# MCU.net
KiCad netlist of a schematic drawn in Altium Designer
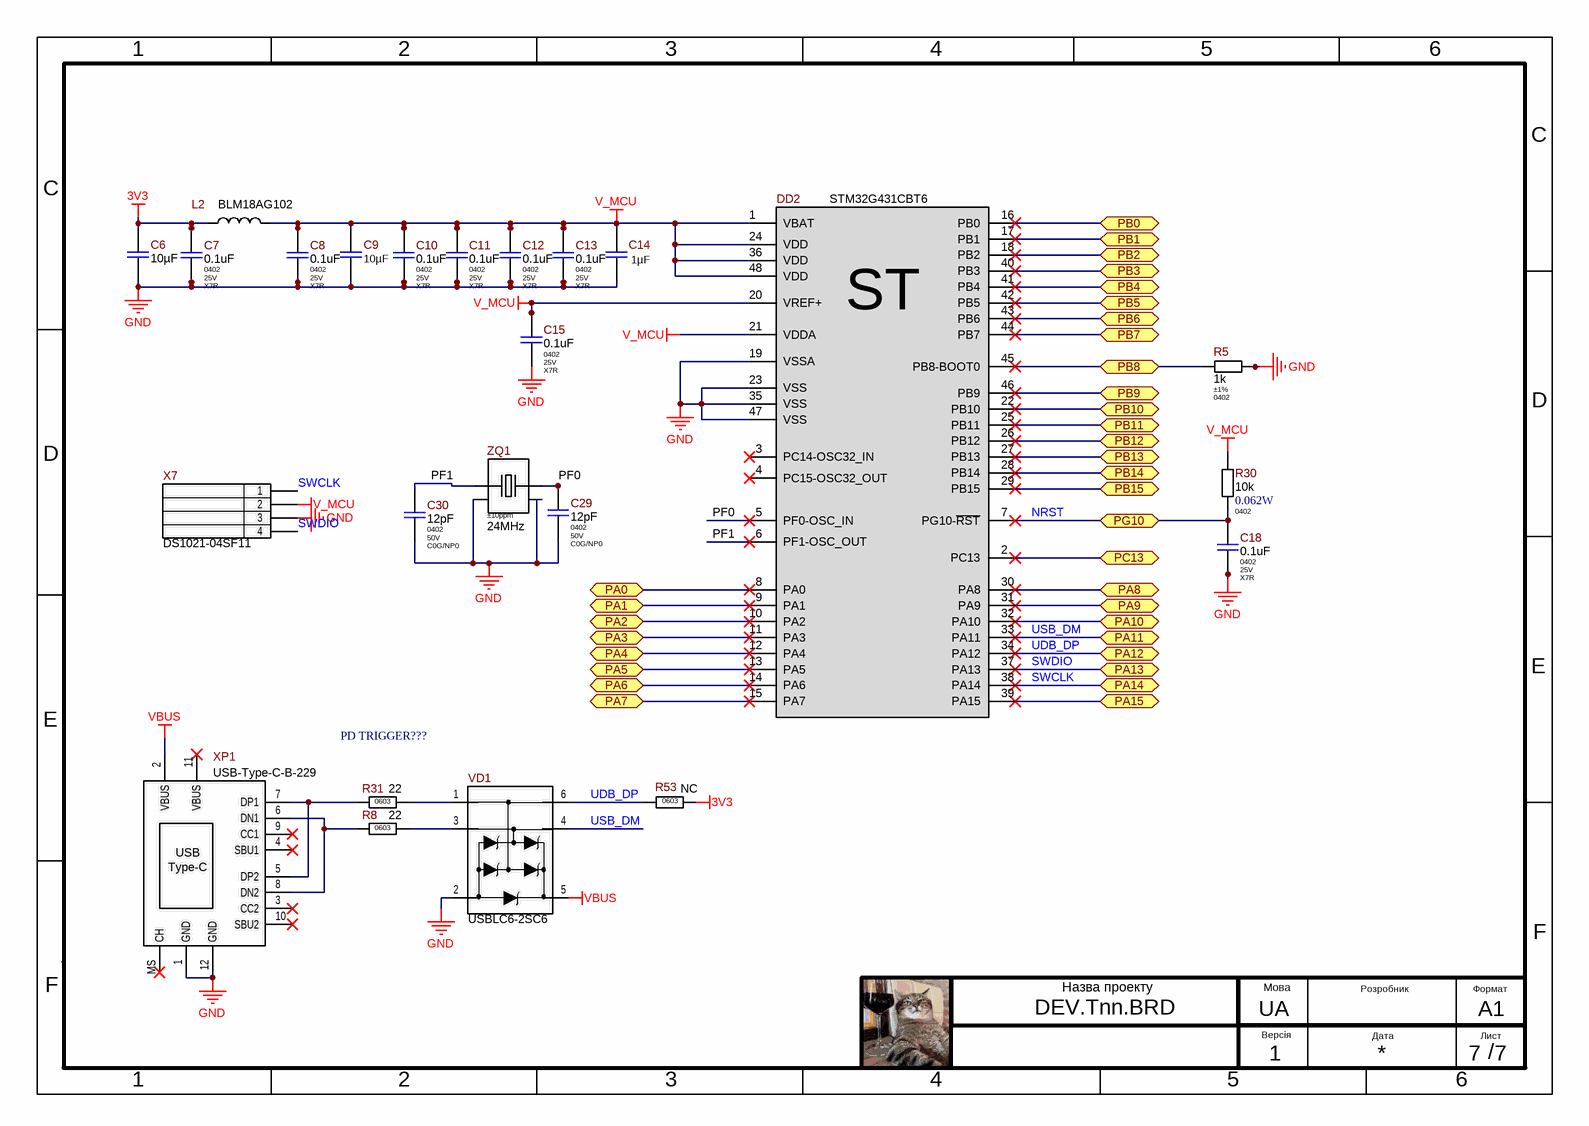
[diagram p0: MCU.SchDoc]

(export (version "E")
  (design (tool "Eeschema 10.0.6"))
  (components
    (comp (ref "C6")
      (value "10µF")
      (footprint "C0603(1608)")
      (description "CAP CER 10UF 6.3V X5R 0603")
      (fields (field (name "PART NUMBER") "10µF  6.3V C0603") (field (name "TOLERANCE") "±20%"))
      (libsource (lib "Database") (part "Capacitor_Ceramic"))
    )
    (comp (ref "C7")
      (value "0.1uF")
      (footprint "C_CERAMIC_0402_MED")
      (description "100nF 25V X7R ±10% 0402 Ceramic Capacitor RoHS")
      (fields
        (field (name "PART NUMBER") "GRM155R71E104KE14J")
        (field (name "TOLERANCE") "±10%")
        (field (name "PACKAGE") "0402")
        (field (name "VOLTAGE") "25V")
        (field (name "DIELECTRIC TYPE") "X7R")
      )
      (libsource (lib "AjaxLibrary") (part "Capacitor-NonPolar"))
    )
    (comp (ref "C8")
      (value "0.1uF")
      (footprint "C_CERAMIC_0402_MED")
      (description "100nF 25V X7R ±10% 0402 Ceramic Capacitor RoHS")
      (fields
        (field (name "PART NUMBER") "GRM155R71E104KE14J")
        (field (name "TOLERANCE") "±10%")
        (field (name "PACKAGE") "0402")
        (field (name "VOLTAGE") "25V")
        (field (name "DIELECTRIC TYPE") "X7R")
      )
      (libsource (lib "AjaxLibrary") (part "Capacitor-NonPolar"))
    )
    (comp (ref "C9")
      (value "10µF")
      (footprint "C0603(1608)")
      (description "CAP CER 10UF 6.3V X5R 0603")
      (fields (field (name "PART NUMBER") "10µF  6.3V C0603") (field (name "TOLERANCE") "±20%"))
      (libsource (lib "Database") (part "Capacitor_Ceramic"))
    )
    (comp (ref "C10")
      (value "0.1uF")
      (footprint "C_CERAMIC_0402_MED")
      (description "100nF 25V X7R ±10% 0402 Ceramic Capacitor RoHS")
      (fields
        (field (name "PART NUMBER") "GRM155R71E104KE14J")
        (field (name "TOLERANCE") "±10%")
        (field (name "PACKAGE") "0402")
        (field (name "VOLTAGE") "25V")
        (field (name "DIELECTRIC TYPE") "X7R")
      )
      (libsource (lib "AjaxLibrary") (part "Capacitor-NonPolar"))
    )
    (comp (ref "C11")
      (value "0.1uF")
      (footprint "C_CERAMIC_0402_MED")
      (description "100nF 25V X7R ±10% 0402 Ceramic Capacitor RoHS")
      (fields
        (field (name "PART NUMBER") "GRM155R71E104KE14J")
        (field (name "TOLERANCE") "±10%")
        (field (name "PACKAGE") "0402")
        (field (name "VOLTAGE") "25V")
        (field (name "DIELECTRIC TYPE") "X7R")
      )
      (libsource (lib "AjaxLibrary") (part "Capacitor-NonPolar"))
    )
    (comp (ref "C12")
      (value "0.1uF")
      (footprint "C_CERAMIC_0402_MED")
      (description "100nF 25V X7R ±10% 0402 Ceramic Capacitor RoHS")
      (fields
        (field (name "PART NUMBER") "GRM155R71E104KE14J")
        (field (name "TOLERANCE") "±10%")
        (field (name "PACKAGE") "0402")
        (field (name "VOLTAGE") "25V")
        (field (name "DIELECTRIC TYPE") "X7R")
      )
      (libsource (lib "AjaxLibrary") (part "Capacitor-NonPolar"))
    )
    (comp (ref "C13")
      (value "0.1uF")
      (footprint "C_CERAMIC_0402_MED")
      (description "100nF 25V X7R ±10% 0402 Ceramic Capacitor RoHS")
      (fields
        (field (name "PART NUMBER") "GRM155R71E104KE14J")
        (field (name "TOLERANCE") "±10%")
        (field (name "PACKAGE") "0402")
        (field (name "VOLTAGE") "25V")
        (field (name "DIELECTRIC TYPE") "X7R")
      )
      (libsource (lib "AjaxLibrary") (part "Capacitor-NonPolar"))
    )
    (comp (ref "C14")
      (value "1µF")
      (footprint "C0603(1608)")
      (description "CAP CER 1UF 25V X5R 0603")
      (fields (field (name "PART NUMBER") "1µF  25V C0603") (field (name "TOLERANCE") "±10%"))
      (libsource (lib "Database") (part "Capacitor_Ceramic"))
    )
    (comp (ref "C15")
      (value "0.1uF")
      (footprint "C_CERAMIC_0402_MED")
      (description "100nF 25V X7R ±10% 0402 Ceramic Capacitor RoHS")
      (fields
        (field (name "PART NUMBER") "GRM155R71E104KE14J")
        (field (name "TOLERANCE") "±10%")
        (field (name "PACKAGE") "0402")
        (field (name "VOLTAGE") "25V")
        (field (name "DIELECTRIC TYPE") "X7R")
      )
      (libsource (lib "AjaxLibrary") (part "Capacitor-NonPolar"))
    )
    (comp (ref "C18")
      (value "0.1uF")
      (footprint "C_CERAMIC_0402_MED")
      (description "100nF 25V X7R ±10% 0402 Ceramic Capacitor RoHS")
      (fields
        (field (name "PART NUMBER") "GRM155R71E104KE14J")
        (field (name "TOLERANCE") "±10%")
        (field (name "PACKAGE") "0402")
        (field (name "VOLTAGE") "25V")
        (field (name "DIELECTRIC TYPE") "X7R")
      )
      (libsource (lib "AjaxLibrary") (part "Capacitor-NonPolar"))
    )
    (comp (ref "C29")
      (value "12pF")
      (footprint "C_CERAMIC_0402_MED")
      (description "12pF 50V C0G ±5% 0402 Ceramic Capacitor RoHS")
      (fields
        (field (name "PART NUMBER") "CL05C120JB5NNNC")
        (field (name "TOLERANCE") "±5%")
        (field (name "PACKAGE") "0402")
        (field (name "VOLTAGE") "50V")
        (field (name "DIELECTRIC TYPE") "C0G/NP0")
      )
      (libsource (lib "AjaxLibrary") (part "Capacitor-NonPolar"))
    )
    (comp (ref "C30")
      (value "12pF")
      (footprint "C_CERAMIC_0402_MED")
      (description "12pF 50V C0G ±5% 0402 Ceramic Capacitor RoHS")
      (fields
        (field (name "PART NUMBER") "CL05C120JB5NNNC")
        (field (name "TOLERANCE") "±5%")
        (field (name "PACKAGE") "0402")
        (field (name "VOLTAGE") "50V")
        (field (name "DIELECTRIC TYPE") "C0G/NP0")
      )
      (libsource (lib "AjaxLibrary") (part "Capacitor-NonPolar"))
    )
    (comp (ref "DD2")
      (value "STM32G431CBT6")
      (footprint "LQFP48")
      (fields (field (name "MF") "STMicroelectronics") (field (name "MP") "STM32G431CBU6"))
      (libsource (lib "Database") (part "STM32G431CBT6"))
    )
    (comp (ref "L2")
      (value "BLM18AG102")
      (footprint "BLM18(0603)")
      (description "FERRITE BEAD 1 KOHM 0603 1LN")
      (fields
        (field (name "TOLERANCE") "±25%")
        (field (name "MANUFACTURER") "Murata Electronics North America")
      )
      (libsource (lib "Database") (part "INDUCTORS"))
    )
    (comp (ref "R5")
      (value "1k")
      (footprint "R_ANY_CHIP_0402_MED")
      (description "1 kOhms ±1% 1/16W 0402 Thick Film Resistor")
      (fields
        (field (name "TOLERANCE") "±1%")
        (field (name "PART NUMBER") "RC0402FR-071KL")
        (field (name "PACKAGE") "0402")
        (field (name "MANUFACTURER") "Yageo")
      )
      (libsource (lib "AjaxLibrary") (part "Resistor"))
    )
    (comp (ref "R8")
      (value "22")
      (footprint "R0603")
      (description "RES SMD 22 OHM  ±1% 1/10W 0603")
      (fields
        (field (name "PACKAGE/CASE") "0603")
        (field (name "PART NUMBER") "22  R0603")
        (field (name "TOLERANCE") "±1%")
      )
      (libsource (lib "Database") (part "R0603"))
    )
    (comp (ref "R30")
      (value "10k")
      (footprint "R_ANY_CHIP_0402_MED")
      (description "10 kOhms ±5% 1/16W 0402 Thick Film Resistor")
      (fields
        (field (name "PART NUMBER") "RC0402JR-0710KL")
        (field (name "TOLERANCE") "±5%")
        (field (name "POWER RATING") "0.062W")
        (field (name "PACKAGE") "0402")
      )
      (libsource (lib "AjaxLibrary") (part "Resistor"))
    )
    (comp (ref "R31")
      (value "22")
      (footprint "R0603")
      (description "RES SMD 22 OHM  ±1% 1/10W 0603")
      (fields
        (field (name "PACKAGE/CASE") "0603")
        (field (name "PART NUMBER") "22  R0603")
        (field (name "TOLERANCE") "±1%")
      )
      (libsource (lib "Database") (part "R0603"))
    )
    (comp (ref "R53")
      (value "NC")
      (footprint "R0603")
      (description "RES SMD 1.5 k OHM  ±1% 1/10W 0603")
      (fields (field (name "PART NUMBER") "1.5 k  R0603") (field (name "PACKAGE/CASE") "0603"))
      (libsource (lib "Database") (part "R0603"))
    )
    (comp (ref "VD1")
      (value "USBLC6-2SC6")
      (footprint "SOT-23-6")
      (description "TVS DIODE 5.25V 17V SOT23-6")
      (fields (field (name "MANUFACTURER") "STMicroelectronics"))
      (libsource (lib "Database") (part "USBLC6-2"))
    )
    (comp (ref "X7")
      (value "PLS-4 (Part of PLS-40)")
      (footprint "DS1021-04S")
      (description "4 Pin 2.54mm Male Header, Vertical, 3mm and 6.1mm, PLS-4")
      (fields (field (name "PART NUMBER") "DS1021-04SF11") (field (name "MANUFACTURER") "Connfly"))
      (libsource (lib "AjaxLibrary") (part "General-4-Pin"))
    )
    (comp (ref "XP1")
      (value "USB-Type-C-B-229")
      (footprint "USB-Type-C-B-229")
      (fields (field (name "MANUFACTURER") "KLS ELECTRONIC CO., LTD."))
      (libsource (lib "Database") (part "USB-Type-C-B-229"))
    )
    (comp (ref "ZQ1")
      (value "C3E-24.000-18-1010-R")
      (footprint "CXA-321_REC")
      (description "24MHz, 18pF, ±10ppm, 100Ohm ESR, 100uW DL Crystal Quartz")
      (fields
        (field (name "FREQUENCY TOLERANCE") "±10ppm")
        (field (name "FREQUENCY") "24MHz")
        (field (name "MANUFACTURER") "Aker")
      )
      (libsource (lib "AjaxLibrary") (part "Crystal-Quartz-4-Pin-01"))
    )
  )
  (nets
    (net (code "1") (name "/NRST") (class "Default")
      (node (ref "C18") (pin "2") (pinfunction "2_2") (pintype "passive"))
      (node (ref "DD2") (pin "7") (pinfunction "PG10-~{RST}_7") (pintype "passive"))
      (node (ref "R30") (pin "2") (pintype "passive"))
    )
    (net (code "2") (name "/PA0") (class "Default")
      (node (ref "DD2") (pin "8") (pinfunction "PA0_8") (pintype "passive+no_connect"))
    )
    (net (code "3") (name "/PA1") (class "Default")
      (node (ref "DD2") (pin "9") (pinfunction "PA1_9") (pintype "passive+no_connect"))
    )
    (net (code "4") (name "/PA2") (class "Default")
      (node (ref "DD2") (pin "10") (pinfunction "PA2_10") (pintype "passive+no_connect"))
    )
    (net (code "5") (name "/PA3") (class "Default")
      (node (ref "DD2") (pin "11") (pinfunction "PA3_11") (pintype "passive+no_connect"))
    )
    (net (code "6") (name "/PA4") (class "Default")
      (node (ref "DD2") (pin "12") (pinfunction "PA4_12") (pintype "passive+no_connect"))
    )
    (net (code "7") (name "/PA5") (class "Default")
      (node (ref "DD2") (pin "13") (pinfunction "PA5_13") (pintype "passive+no_connect"))
    )
    (net (code "8") (name "/PA6") (class "Default")
      (node (ref "DD2") (pin "14") (pinfunction "PA6_14") (pintype "passive+no_connect"))
    )
    (net (code "9") (name "/PA7") (class "Default")
      (node (ref "DD2") (pin "15") (pinfunction "PA7_15") (pintype "passive+no_connect"))
    )
    (net (code "10") (name "/PA8") (class "Default")
      (node (ref "DD2") (pin "30") (pinfunction "PA8_30") (pintype "passive+no_connect"))
    )
    (net (code "11") (name "/PA9") (class "Default")
      (node (ref "DD2") (pin "31") (pinfunction "PA9_31") (pintype "passive+no_connect"))
    )
    (net (code "12") (name "/PA10") (class "Default")
      (node (ref "DD2") (pin "32") (pinfunction "PA10_32") (pintype "passive+no_connect"))
    )
    (net (code "13") (name "/PA15") (class "Default")
      (node (ref "DD2") (pin "39") (pinfunction "PA15_39") (pintype "passive+no_connect"))
    )
    (net (code "14") (name "/PB0") (class "Default")
      (node (ref "DD2") (pin "16") (pinfunction "PB0_16") (pintype "passive+no_connect"))
    )
    (net (code "15") (name "/PB1") (class "Default")
      (node (ref "DD2") (pin "17") (pinfunction "PB1_17") (pintype "passive+no_connect"))
    )
    (net (code "16") (name "/PB2") (class "Default")
      (node (ref "DD2") (pin "18") (pinfunction "PB2_18") (pintype "passive+no_connect"))
    )
    (net (code "17") (name "/PB3") (class "Default")
      (node (ref "DD2") (pin "40") (pinfunction "PB3_40") (pintype "passive+no_connect"))
    )
    (net (code "18") (name "/PB4") (class "Default")
      (node (ref "DD2") (pin "41") (pinfunction "PB4_41") (pintype "passive+no_connect"))
    )
    (net (code "19") (name "/PB5") (class "Default")
      (node (ref "DD2") (pin "42") (pinfunction "PB5_42") (pintype "passive+no_connect"))
    )
    (net (code "20") (name "/PB6") (class "Default")
      (node (ref "DD2") (pin "43") (pinfunction "PB6_43") (pintype "passive+no_connect"))
    )
    (net (code "21") (name "/PB7") (class "Default")
      (node (ref "DD2") (pin "44") (pinfunction "PB7_44") (pintype "passive+no_connect"))
    )
    (net (code "22") (name "/PB8") (class "Default")
      (node (ref "DD2") (pin "45") (pinfunction "PB8-BOOT0_45") (pintype "passive"))
      (node (ref "R5") (pin "1") (pintype "passive"))
    )
    (net (code "23") (name "/PB9") (class "Default")
      (node (ref "DD2") (pin "46") (pinfunction "PB9_46") (pintype "passive+no_connect"))
    )
    (net (code "24") (name "/PB10") (class "Default")
      (node (ref "DD2") (pin "22") (pinfunction "PB10_22") (pintype "passive+no_connect"))
    )
    (net (code "25") (name "/PB11") (class "Default")
      (node (ref "DD2") (pin "25") (pinfunction "PB11_25") (pintype "passive+no_connect"))
    )
    (net (code "26") (name "/PB12") (class "Default")
      (node (ref "DD2") (pin "26") (pinfunction "PB12_26") (pintype "passive+no_connect"))
    )
    (net (code "27") (name "/PB13") (class "Default")
      (node (ref "DD2") (pin "27") (pinfunction "PB13_27") (pintype "passive+no_connect"))
    )
    (net (code "28") (name "/PB14") (class "Default")
      (node (ref "DD2") (pin "28") (pinfunction "PB14_28") (pintype "passive+no_connect"))
    )
    (net (code "29") (name "/PB15") (class "Default")
      (node (ref "DD2") (pin "29") (pinfunction "PB15_29") (pintype "passive+no_connect"))
    )
    (net (code "30") (name "/PC13") (class "Default")
      (node (ref "DD2") (pin "2") (pinfunction "PC13_2") (pintype "passive+no_connect"))
    )
    (net (code "31") (name "/PF0") (class "Default")
      (node (ref "C29") (pin "1") (pinfunction "1_1") (pintype "passive"))
      (node (ref "DD2") (pin "5") (pinfunction "PF0-OSC_IN_5") (pintype "passive"))
      (node (ref "ZQ1") (pin "3") (pinfunction "XTAL2_3") (pintype "passive"))
    )
    (net (code "32") (name "/PF1") (class "Default")
      (node (ref "C30") (pin "1") (pinfunction "1_1") (pintype "passive"))
      (node (ref "DD2") (pin "6") (pinfunction "PF1-OSC_OUT_6") (pintype "passive"))
      (node (ref "ZQ1") (pin "1") (pinfunction "XTAL1_1") (pintype "passive"))
    )
    (net (code "33") (name "/SWCLK") (class "Default")
      (node (ref "DD2") (pin "38") (pinfunction "PA14_38") (pintype "passive"))
      (node (ref "X7") (pin "1") (pinfunction "1_1") (pintype "passive"))
    )
    (net (code "34") (name "/SWDIO") (class "Default")
      (node (ref "DD2") (pin "37") (pinfunction "PA13_37") (pintype "passive"))
      (node (ref "X7") (pin "4") (pinfunction "4_4") (pintype "passive"))
    )
    (net (code "35") (name "/UDB_DP") (class "Default")
      (node (ref "DD2") (pin "34") (pinfunction "PA12_34") (pintype "passive"))
      (node (ref "R53") (pin "1") (pinfunction "1_1") (pintype "passive"))
      (node (ref "VD1") (pin "6") (pinfunction "D+OUT_6") (pintype "passive"))
    )
    (net (code "36") (name "/USB_DM") (class "Default")
      (node (ref "DD2") (pin "33") (pinfunction "PA11_33") (pintype "passive"))
      (node (ref "VD1") (pin "4") (pinfunction "D-OUT_4") (pintype "passive"))
    )
    (net (code "37") (name "3V3") (class "Default")
      (node (ref "C6") (pin "1") (pinfunction "1_1") (pintype "passive"))
      (node (ref "C7") (pin "2") (pinfunction "2_2") (pintype "passive"))
      (node (ref "L2") (pin "1") (pintype "passive"))
      (node (ref "R53") (pin "2") (pinfunction "2_2") (pintype "passive"))
    )
    (net (code "38") (name "GND") (class "Default")
      (node (ref "C10") (pin "1") (pinfunction "1_1") (pintype "passive"))
      (node (ref "C11") (pin "1") (pinfunction "1_1") (pintype "passive"))
      (node (ref "C12") (pin "1") (pinfunction "1_1") (pintype "passive"))
      (node (ref "C13") (pin "1") (pinfunction "1_1") (pintype "passive"))
      (node (ref "C14") (pin "2") (pinfunction "2_2") (pintype "passive"))
      (node (ref "C15") (pin "1") (pinfunction "1_1") (pintype "passive"))
      (node (ref "C18") (pin "1") (pinfunction "1_1") (pintype "passive"))
      (node (ref "C29") (pin "2") (pinfunction "2_2") (pintype "passive"))
      (node (ref "C30") (pin "2") (pinfunction "2_2") (pintype "passive"))
      (node (ref "C6") (pin "2") (pinfunction "2_2") (pintype "passive"))
      (node (ref "C7") (pin "1") (pinfunction "1_1") (pintype "passive"))
      (node (ref "C8") (pin "1") (pinfunction "1_1") (pintype "passive"))
      (node (ref "C9") (pin "2") (pinfunction "2_2") (pintype "passive"))
      (node (ref "DD2") (pin "19") (pinfunction "VSSA_19") (pintype "passive"))
      (node (ref "DD2") (pin "23") (pinfunction "VSS_23") (pintype "passive"))
      (node (ref "DD2") (pin "35") (pinfunction "VSS_35") (pintype "passive"))
      (node (ref "DD2") (pin "47") (pinfunction "VSS_47") (pintype "passive"))
      (node (ref "R5") (pin "2") (pintype "passive"))
      (node (ref "VD1") (pin "2") (pinfunction "GND_2") (pintype "passive"))
      (node (ref "X7") (pin "3") (pinfunction "3_3") (pintype "passive"))
      (node (ref "XP1") (pin "1") (pinfunction "GND_1") (pintype "passive"))
      (node (ref "XP1") (pin "12") (pinfunction "GND_12") (pintype "passive"))
      (node (ref "ZQ1") (pin "2") (pinfunction "NC1_2") (pintype "passive"))
      (node (ref "ZQ1") (pin "4") (pinfunction "NC2_4") (pintype "passive"))
    )
    (net (code "39") (name "Net-(VD1-D+IN)") (class "Default")
      (node (ref "R31") (pin "2") (pinfunction "2_2") (pintype "passive"))
      (node (ref "VD1") (pin "1") (pinfunction "D+IN_1") (pintype "passive"))
    )
    (net (code "40") (name "Net-(VD1-D-IN)") (class "Default")
      (node (ref "R8") (pin "2") (pinfunction "2_2") (pintype "passive"))
      (node (ref "VD1") (pin "3") (pinfunction "D-IN_3") (pintype "passive"))
    )
    (net (code "41") (name "Net-(XP1-DN1)") (class "Default")
      (node (ref "R8") (pin "1") (pinfunction "1_1") (pintype "passive"))
      (node (ref "XP1") (pin "6") (pinfunction "DN1_6") (pintype "passive"))
      (node (ref "XP1") (pin "8") (pinfunction "DN2_8") (pintype "passive"))
    )
    (net (code "42") (name "Net-(XP1-DP1)") (class "Default")
      (node (ref "R31") (pin "1") (pinfunction "1_1") (pintype "passive"))
      (node (ref "XP1") (pin "5") (pinfunction "DP2_5") (pintype "passive"))
      (node (ref "XP1") (pin "7") (pinfunction "DP1_7") (pintype "passive"))
    )
    (net (code "43") (name "VBUS") (class "Default")
      (node (ref "VD1") (pin "5") (pinfunction "VBUS_5") (pintype "passive"))
      (node (ref "XP1") (pin "2") (pinfunction "VBUS_2") (pintype "passive"))
    )
    (net (code "44") (name "V_MCU") (class "Default")
      (node (ref "C10") (pin "2") (pinfunction "2_2") (pintype "passive"))
      (node (ref "C11") (pin "2") (pinfunction "2_2") (pintype "passive"))
      (node (ref "C12") (pin "2") (pinfunction "2_2") (pintype "passive"))
      (node (ref "C13") (pin "2") (pinfunction "2_2") (pintype "passive"))
      (node (ref "C14") (pin "1") (pinfunction "1_1") (pintype "passive"))
      (node (ref "C15") (pin "2") (pinfunction "2_2") (pintype "passive"))
      (node (ref "C8") (pin "2") (pinfunction "2_2") (pintype "passive"))
      (node (ref "C9") (pin "1") (pinfunction "1_1") (pintype "passive"))
      (node (ref "DD2") (pin "1") (pinfunction "VBAT_1") (pintype "passive"))
      (node (ref "DD2") (pin "20") (pinfunction "VREF+_20") (pintype "passive"))
      (node (ref "DD2") (pin "21") (pinfunction "VDDA_21") (pintype "passive"))
      (node (ref "DD2") (pin "24") (pinfunction "VDD_24") (pintype "passive"))
      (node (ref "DD2") (pin "36") (pinfunction "VDD_36") (pintype "passive"))
      (node (ref "DD2") (pin "48") (pinfunction "VDD_48") (pintype "passive"))
      (node (ref "L2") (pin "2") (pintype "passive"))
      (node (ref "R30") (pin "1") (pintype "passive"))
      (node (ref "X7") (pin "2") (pinfunction "2_2") (pintype "passive"))
    )
    (net (code "45") (name "unconnected-(DD2-PC14-OSC32_IN-Pad3)") (class "Default")
      (node (ref "DD2") (pin "3") (pinfunction "PC14-OSC32_IN_3") (pintype "passive+no_connect"))
    )
    (net (code "46") (name "unconnected-(DD2-PC15-OSC32_OUT-Pad4)") (class "Default")
      (node (ref "DD2") (pin "4") (pinfunction "PC15-OSC32_OUT_4") (pintype "passive+no_connect"))
    )
    (net (code "47") (name "unconnected-(XP1-CC1-Pad9)") (class "Default")
      (node (ref "XP1") (pin "9") (pinfunction "CC1_9") (pintype "passive+no_connect"))
    )
    (net (code "48") (name "unconnected-(XP1-CC2-Pad3)") (class "Default")
      (node (ref "XP1") (pin "3") (pinfunction "CC2_3") (pintype "passive+no_connect"))
    )
    (net (code "49") (name "unconnected-(XP1-CH-PadMS)") (class "Default")
      (node (ref "XP1") (pin "MS") (pinfunction "CH_MS") (pintype "passive+no_connect"))
    )
    (net (code "50") (name "unconnected-(XP1-SBU1-Pad4)") (class "Default")
      (node (ref "XP1") (pin "4") (pinfunction "SBU1_4") (pintype "passive+no_connect"))
    )
    (net (code "51") (name "unconnected-(XP1-SBU2-Pad10)") (class "Default")
      (node (ref "XP1") (pin "10") (pinfunction "SBU2_10") (pintype "passive+no_connect"))
    )
    (net (code "52") (name "unconnected-(XP1-VBUS-Pad11)") (class "Default")
      (node (ref "XP1") (pin "11") (pinfunction "VBUS_11") (pintype "passive+no_connect"))
    )
  )
)
